# BoostStage.net
KiCad netlist of a schematic drawn in Altium Designer
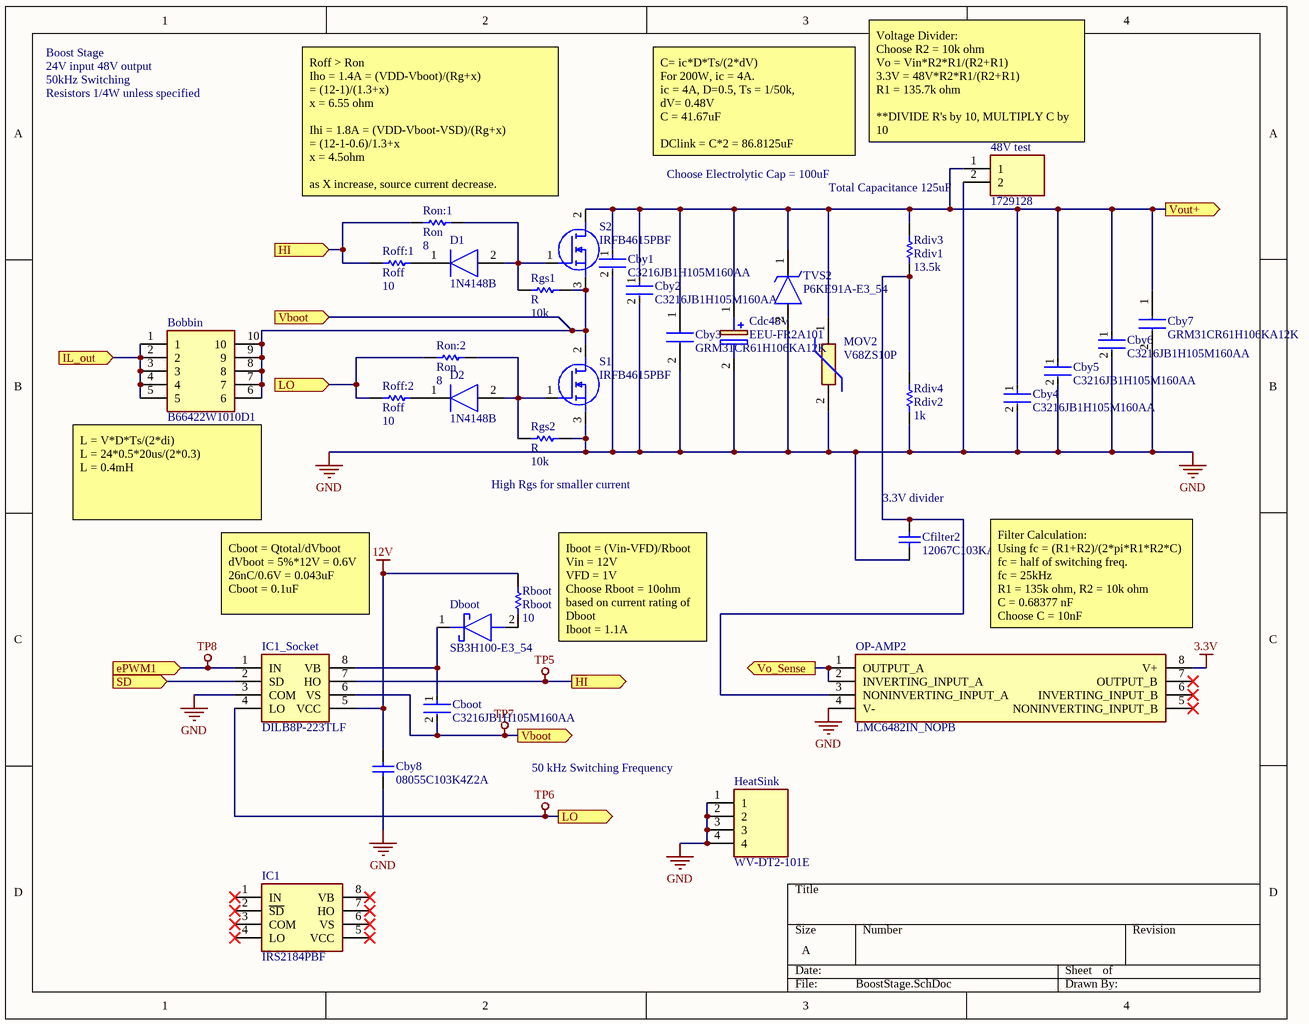
[diagram p0: BoostStage.SchDoc]

(export (version "E")
  (design (tool "Eeschema 10.0.6"))
  (components
    (comp (ref "48V test")
      (value "1729128")
      (footprint "SamacSys:HDRV2W110P0X508_1X2_1016X810X1000P")
      (description "Connector")
      (fields (field (name "MOUSER PART NUMBER") "651-1729128"))
      (libsource (lib "*") (part "1729128"))
    )
    (comp (ref "Bobbin")
      (value "B66422W1010D1")
      (footprint "B66422W1010D1")
      (description "Bobbin")
      (fields (field (name "MOUSER2 PART NUMBER") "871-B66422W1010D1"))
      (libsource (lib "ee_453_yourname") (part "B66422W1010D1"))
    )
    (comp (ref "Cboot")
      (value "C3216JB1H105M160AA")
      (footprint "FP-C3216-160-0_2-IPC_B")
      (description "Multilayer Ceramic Capacitors 1uF ±20% 50V JB SMD 1206")
      (fields (field (name "TOLERANCE") "20%"))
      (libsource (lib "Altium Content Vault") (part "11868f565c42a9108669ba33697ecf6"))
    )
    (comp (ref "Cby1")
      (value "C3216JB1H105M160AA")
      (footprint "FP-C3216-160-0_2-IPC_B")
      (description "Multilayer Ceramic Capacitors 1uF ±20% 50V JB SMD 1206")
      (fields (field (name "TOLERANCE") "20%"))
      (libsource (lib "Altium Content Vault") (part "11868f565c42a9108669ba33697ecf6"))
    )
    (comp (ref "Cby2")
      (value "C3216JB1H105M160AA")
      (footprint "FP-C3216-160-0_2-IPC_B")
      (description "Multilayer Ceramic Capacitors 1uF ±20% 50V JB SMD 1206")
      (fields (field (name "TOLERANCE") "20%"))
      (libsource (lib "Altium Content Vault") (part "11868f565c42a9108669ba33697ecf6"))
    )
    (comp (ref "Cby3")
      (value "GRM31CR61H106KA12K")
      (footprint "SamacSys:CAPC3216X180N")
      (description "Capacitor Ceramic 10uF")
      (fields (field (name "MOUSER PART NUMBER") "81-GRM31CR61H106KA2K"))
      (libsource (lib "*") (part "GRM31CR61H106KA12K"))
    )
    (comp (ref "Cby4")
      (value "C3216JB1H105M160AA")
      (footprint "FP-C3216-160-0_2-IPC_B")
      (description "Multilayer Ceramic Capacitors 1uF ±20% 50V JB SMD 1206")
      (fields (field (name "TOLERANCE") "20%"))
      (libsource (lib "Altium Content Vault") (part "11868f565c42a9108669ba33697ecf6"))
    )
    (comp (ref "Cby5")
      (value "C3216JB1H105M160AA")
      (footprint "FP-C3216-160-0_2-IPC_B")
      (description "Multilayer Ceramic Capacitors 1uF ±20% 50V JB SMD 1206")
      (fields (field (name "TOLERANCE") "20%"))
      (libsource (lib "Altium Content Vault") (part "11868f565c42a9108669ba33697ecf6"))
    )
    (comp (ref "Cby6")
      (value "C3216JB1H105M160AA")
      (footprint "FP-C3216-160-0_2-IPC_B")
      (description "Multilayer Ceramic Capacitors 1uF ±20% 50V JB SMD 1206")
      (fields (field (name "TOLERANCE") "20%"))
      (libsource (lib "Altium Content Vault") (part "11868f565c42a9108669ba33697ecf6"))
    )
    (comp (ref "Cby7")
      (value "GRM31CR61H106KA12K")
      (footprint "SamacSys:CAPC3216X180N")
      (description "Capacitor Ceramic 10uF")
      (fields (field (name "MOUSER PART NUMBER") "81-GRM31CR61H106KA2K"))
      (libsource (lib "*") (part "GRM31CR61H106KA12K"))
    )
    (comp (ref "Cby8")
      (value "08055C103K4Z2A")
      (footprint "CAPC2013X94X50NL20T25")
      (fields (field (name "MANUFACTURER") "AVX Interconnect / Elco"))
      (libsource (lib "Altium Content Vault") (part "CAP"))
    )
    (comp (ref "Cdc48V")
      (value "EEU-FR2A101")
      (footprint "SamacSys:CAPPRD500W65D1000H2200")
      (description "100uF Capacitor Polarised")
      (fields (field (name "MOUSER PART NUMBER") "667-EEU-FR2A101"))
      (libsource (lib "*") (part "EEU-FR2A101"))
    )
    (comp (ref "Cfilter2")
      (value "12067C103KAT2A")
      (footprint "CAPC1206(3216)170_N")
      (description "CAP 10nF 500V ±10% 1206 (3216 Metric) Thickness 1.7mm SMD")
      (fields (field (name "TOLERANCE") "Â±10%"))
      (libsource (lib "Altium Content Vault") (part "CAP"))
    )
    (comp (ref "D1")
      (value "1N4148B")
      (footprint "SamacSys:DIOAD990W55L340D162")
      (description "Diode")
      (libsource (lib "*") (part "1N4148B"))
    )
    (comp (ref "D2")
      (value "1N4148B")
      (footprint "SamacSys:DIOAD990W55L340D162")
      (description "Diode")
      (libsource (lib "*") (part "1N4148B"))
    )
    (comp (ref "Dboot")
      (value "SB3H100-E3_54")
      (footprint "SamacSys:DIOAD2855W132L835D505")
      (description "Schottky Diode")
      (fields
        (field (name "MANUFACTURER_PART_NUMBER") "SB3H100-E3/54")
        (field (name "MOUSER PART NUMBER") "625-SB3H100-E3")
      )
      (libsource (lib "*") (part "SB3H100-E3_54"))
    )
    (comp (ref "HeatSink")
      (value "WV-DT2-101E")
      (footprint "SamacSys:WVDT2101E")
      (description "Hardware")
      (fields (field (name "MOUSER PART NUMBER") "588-WV-DT2-101E"))
      (libsource (lib "*") (part "WV-DT2-101E"))
    )
    (comp (ref "IC1")
      (value "IRS2184PBF")
      (footprint "SamacSys:DIP762W56P254L988H533Q8N")
      (description "Integrated Circuit")
      (fields (field (name "MOUSER PART NUMBER") "942-IRS2184PBF"))
      (libsource (lib "*") (part "IRS2184PBF"))
    )
    (comp (ref "IC1_Socket")
      (value "DILB8P-223TLF")
      (footprint "DIPS762W60P254L1016H525Q8N")
      (description "Connector")
      (fields (field (name "MOUSER2 PART NUMBER") "649-DILB8P223TLF"))
      (libsource (lib "ee_453_yourname") (part "DILB8P-223TLF"))
    )
    (comp (ref "MOV2")
      (value "V68ZS10P")
      (footprint "SamacSys:V68ZS10P")
      (description "Varistor")
      (fields (field (name "MOUSER PART NUMBER") "576-V68ZS10P"))
      (libsource (lib "*") (part "V68ZS10P"))
    )
    (comp (ref "OP-AMP2")
      (value "LMC6482IN_NOPB")
      (footprint "SamacSys:DIP794W53P254L959H508Q8N")
      (description "Integrated Circuit")
      (fields
        (field (name "MANUFACTURER_PART_NUMBER") "LMC6482IN/NOPB")
        (field (name "MOUSER PART NUMBER") "926-LMC6482IN/NOPB")
      )
      (libsource (lib "*") (part "LMC6482IN_NOPB"))
    )
    (comp (ref "Rboot")
      (value "Rboot")
      (footprint "AXIAL-0.3")
      (description "1/2W 10ohm Resistor")
      (fields (field (name "ALTIUM_VALUE") "10") (field (name "PUBLISHER") "Altium Limited"))
      (libsource (lib "Miscellaneous Devices") (part "Res1"))
    )
    (comp (ref "Rdiv3")
      (value "Rdiv1")
      (footprint "AXIAL-0.3")
      (description "1/4W 135.455k ohm Resistor")
      (fields (field (name "ALTIUM_VALUE") "13.5k") (field (name "PUBLISHER") "Altium Limited"))
      (libsource (lib "Miscellaneous Devices") (part "Res1"))
    )
    (comp (ref "Rdiv4")
      (value "Rdiv2")
      (footprint "AXIAL-0.3")
      (description "1/4W 10k ohm Resistor")
      (fields (field (name "ALTIUM_VALUE") "1k") (field (name "PUBLISHER") "Altium Limited"))
      (libsource (lib "Miscellaneous Devices") (part "Res1"))
    )
    (comp (ref "Rgs1")
      (value "R")
      (footprint "AXIAL-0.3")
      (description "1/4W 10k ohm Resistor")
      (fields (field (name "ALTIUM_VALUE") "10k") (field (name "PUBLISHER") "Altium Limited"))
      (libsource (lib "Miscellaneous Devices") (part "Res1"))
    )
    (comp (ref "Rgs2")
      (value "R")
      (footprint "AXIAL-0.3")
      (description "1/4W 10k ohm Resistor")
      (fields (field (name "ALTIUM_VALUE") "10k") (field (name "PUBLISHER") "Altium Limited"))
      (libsource (lib "Miscellaneous Devices") (part "Res1"))
    )
    (comp (ref "Roff:1")
      (value "Roff")
      (footprint "AXIAL-0.3")
      (description "1/4W 10ohm Resistor")
      (fields (field (name "ALTIUM_VALUE") "10") (field (name "PUBLISHER") "Altium Limited"))
      (libsource (lib "Miscellaneous Devices") (part "Res1"))
    )
    (comp (ref "Roff:2")
      (value "Roff")
      (footprint "AXIAL-0.3")
      (description "1/4W 10ohm Resistor")
      (fields (field (name "ALTIUM_VALUE") "10") (field (name "PUBLISHER") "Altium Limited"))
      (libsource (lib "Miscellaneous Devices") (part "Res1"))
    )
    (comp (ref "Ron:1")
      (value "Ron")
      (footprint "AXIAL-0.3")
      (description "1/4W 8ohm Resistor")
      (fields (field (name "ALTIUM_VALUE") "8") (field (name "PUBLISHER") "Altium Limited"))
      (libsource (lib "Miscellaneous Devices") (part "Res1"))
    )
    (comp (ref "Ron:2")
      (value "Ron")
      (footprint "AXIAL-0.3")
      (description "1/4W 8ohm Resistor")
      (fields (field (name "ALTIUM_VALUE") "8") (field (name "PUBLISHER") "Altium Limited"))
      (libsource (lib "Miscellaneous Devices") (part "Res1"))
    )
    (comp (ref "S1")
      (value "IRFB4615PBF")
      (footprint "SamacSys:TO254P483X1016X1994-3P")
      (description "MOSFET (N-Channel)")
      (fields (field (name "MOUSER PART NUMBER") "942-IRFB4615PBF"))
      (libsource (lib "*") (part "IRFB4615PBF"))
    )
    (comp (ref "S2")
      (value "IRFB4615PBF")
      (footprint "SamacSys:TO254P483X1016X1994-3P")
      (description "MOSFET (N-Channel)")
      (fields (field (name "MOUSER PART NUMBER") "942-IRFB4615PBF"))
      (libsource (lib "*") (part "IRFB4615PBF"))
    )
    (comp (ref "TVS2")
      (value "P6KE91A-E3_54")
      (footprint "SamacSys:DIOAD1910W86L670D310")
      (description "TVS Diode (Uni-directional)")
      (fields (field (name "MANUFACTURER_PART_NUMBER") "P6KE91A-E3/54"))
      (libsource (lib "*") (part "P6KE91A-E3_54"))
    )
  )
  (nets
    (net (code "1") (name "/IL_out") (class "Default")
      (node (ref "Bobbin") (pin "1") (pinfunction "1_1") (pintype "passive"))
      (node (ref "Bobbin") (pin "2") (pinfunction "2_2") (pintype "passive"))
      (node (ref "Bobbin") (pin "3") (pinfunction "3_3") (pintype "passive"))
      (node (ref "Bobbin") (pin "4") (pinfunction "4_4") (pintype "passive"))
      (node (ref "Bobbin") (pin "5") (pinfunction "5_5") (pintype "passive"))
    )
    (net (code "2") (name "/SD") (class "Default")
      (node (ref "IC1_Socket") (pin "2") (pinfunction "SD_2") (pintype "passive"))
    )
    (net (code "3") (name "/Vo_Sense") (class "Default")
      (node (ref "OP-AMP2") (pin "1") (pinfunction "OUTPUT_A_1") (pintype "passive"))
      (node (ref "OP-AMP2") (pin "2") (pinfunction "INVERTING_INPUT_A_2") (pintype "passive"))
    )
    (net (code "4") (name "/Vout+") (class "Default")
      (node (ref "48V test") (pin "1") (pinfunction "1_1") (pintype "passive"))
      (node (ref "Cby1") (pin "1") (pinfunction "1_1") (pintype "passive"))
      (node (ref "Cby2") (pin "1") (pinfunction "1_1") (pintype "passive"))
      (node (ref "Cby3") (pin "1") (pinfunction "1_1") (pintype "passive"))
      (node (ref "Cby4") (pin "1") (pinfunction "1_1") (pintype "passive"))
      (node (ref "Cby5") (pin "1") (pinfunction "1_1") (pintype "passive"))
      (node (ref "Cby6") (pin "1") (pinfunction "1_1") (pintype "passive"))
      (node (ref "Cby7") (pin "1") (pinfunction "1_1") (pintype "passive"))
      (node (ref "Cdc48V") (pin "1") (pinfunction "+_1") (pintype "passive"))
      (node (ref "MOV2") (pin "1") (pinfunction "1_1") (pintype "passive"))
      (node (ref "Rdiv3") (pin "2") (pinfunction "2_2") (pintype "passive"))
      (node (ref "S2") (pin "2") (pinfunction "D_2") (pintype "passive"))
      (node (ref "TVS2") (pin "1") (pinfunction "K_1") (pintype "passive"))
    )
    (net (code "5") (name "3.3V") (class "Default")
      (node (ref "OP-AMP2") (pin "8") (pinfunction "V+_8") (pintype "passive"))
    )
    (net (code "6") (name "12V") (class "Default")
      (node (ref "Cby8") (pin "1") (pinfunction "1_1") (pintype "passive"))
      (node (ref "IC1_Socket") (pin "5") (pinfunction "VCC_5") (pintype "passive"))
      (node (ref "Rboot") (pin "2") (pinfunction "2_2") (pintype "passive"))
    )
    (net (code "7") (name "GND") (class "Default")
      (node (ref "48V test") (pin "2") (pinfunction "2_2") (pintype "passive"))
      (node (ref "Cby1") (pin "2") (pinfunction "2_2") (pintype "passive"))
      (node (ref "Cby2") (pin "2") (pinfunction "2_2") (pintype "passive"))
      (node (ref "Cby3") (pin "2") (pinfunction "2_2") (pintype "passive"))
      (node (ref "Cby4") (pin "2") (pinfunction "2_2") (pintype "passive"))
      (node (ref "Cby5") (pin "2") (pinfunction "2_2") (pintype "passive"))
      (node (ref "Cby6") (pin "2") (pinfunction "2_2") (pintype "passive"))
      (node (ref "Cby7") (pin "2") (pinfunction "2_2") (pintype "passive"))
      (node (ref "Cby8") (pin "2") (pinfunction "2_2") (pintype "passive"))
      (node (ref "Cdc48V") (pin "2") (pinfunction "-_2") (pintype "passive"))
      (node (ref "Cfilter2") (pin "1") (pinfunction "1_1") (pintype "passive"))
      (node (ref "HeatSink") (pin "1") (pinfunction "1_1") (pintype "passive"))
      (node (ref "HeatSink") (pin "2") (pinfunction "2_2") (pintype "passive"))
      (node (ref "HeatSink") (pin "3") (pinfunction "3_3") (pintype "passive"))
      (node (ref "HeatSink") (pin "4") (pinfunction "4_4") (pintype "passive"))
      (node (ref "IC1_Socket") (pin "3") (pinfunction "COM_3") (pintype "passive"))
      (node (ref "MOV2") (pin "2") (pinfunction "2_2") (pintype "passive"))
      (node (ref "OP-AMP2") (pin "4") (pinfunction "V-_4") (pintype "passive"))
      (node (ref "Rdiv4") (pin "1") (pinfunction "1_1") (pintype "passive"))
      (node (ref "Rgs2") (pin "2") (pinfunction "2_2") (pintype "passive"))
      (node (ref "S1") (pin "3") (pinfunction "S_3") (pintype "passive"))
      (node (ref "TVS2") (pin "2") (pinfunction "A_2") (pintype "passive"))
    )
    (net (code "8") (name "Net-(D1-A)") (class "Default")
      (node (ref "D1") (pin "2") (pinfunction "A_2") (pintype "passive"))
      (node (ref "Rgs1") (pin "1") (pinfunction "1_1") (pintype "passive"))
      (node (ref "Ron:1") (pin "2") (pinfunction "2_2") (pintype "passive"))
      (node (ref "S2") (pin "1") (pinfunction "G_1") (pintype "passive"))
    )
    (net (code "9") (name "Net-(D1-K)") (class "Default")
      (node (ref "D1") (pin "1") (pinfunction "K_1") (pintype "passive"))
      (node (ref "Roff:1") (pin "2") (pinfunction "2_2") (pintype "passive"))
    )
    (net (code "10") (name "Net-(D2-A)") (class "Default")
      (node (ref "D2") (pin "2") (pinfunction "A_2") (pintype "passive"))
      (node (ref "Rgs2") (pin "1") (pinfunction "1_1") (pintype "passive"))
      (node (ref "Ron:2") (pin "2") (pinfunction "2_2") (pintype "passive"))
      (node (ref "S1") (pin "1") (pinfunction "G_1") (pintype "passive"))
    )
    (net (code "11") (name "Net-(D2-K)") (class "Default")
      (node (ref "D2") (pin "1") (pinfunction "K_1") (pintype "passive"))
      (node (ref "Roff:2") (pin "2") (pinfunction "2_2") (pintype "passive"))
    )
    (net (code "12") (name "Net-(Dboot-A)") (class "Default")
      (node (ref "Dboot") (pin "2") (pinfunction "A_2") (pintype "passive"))
      (node (ref "Rboot") (pin "1") (pinfunction "1_1") (pintype "passive"))
    )
    (net (code "13") (name "Net-(Dboot-K)") (class "Default")
      (node (ref "Cboot") (pin "1") (pinfunction "1_1") (pintype "passive"))
      (node (ref "Dboot") (pin "1") (pinfunction "K_1") (pintype "passive"))
      (node (ref "IC1_Socket") (pin "8") (pinfunction "VB_8") (pintype "passive"))
    )
    (net (code "14") (name "Net-(OP-AMP2-NONINVERTING_INPUT_A)") (class "Default")
      (node (ref "Cfilter2") (pin "2") (pinfunction "2_2") (pintype "passive"))
      (node (ref "OP-AMP2") (pin "3") (pinfunction "NONINVERTING_INPUT_A_3") (pintype "passive"))
      (node (ref "Rdiv3") (pin "1") (pinfunction "1_1") (pintype "passive"))
      (node (ref "Rdiv4") (pin "2") (pinfunction "2_2") (pintype "passive"))
    )
    (net (code "15") (name "TP5") (class "Default")
      (node (ref "IC1_Socket") (pin "7") (pinfunction "HO_7") (pintype "passive"))
      (node (ref "Roff:1") (pin "1") (pinfunction "1_1") (pintype "passive"))
      (node (ref "Ron:1") (pin "1") (pinfunction "1_1") (pintype "passive"))
    )
    (net (code "16") (name "TP6") (class "Default")
      (node (ref "IC1_Socket") (pin "4") (pinfunction "LO_4") (pintype "passive"))
      (node (ref "Roff:2") (pin "1") (pinfunction "1_1") (pintype "passive"))
      (node (ref "Ron:2") (pin "1") (pinfunction "1_1") (pintype "passive"))
    )
    (net (code "17") (name "TP7") (class "Default")
      (node (ref "Bobbin") (pin "10") (pinfunction "10_10") (pintype "passive"))
      (node (ref "Bobbin") (pin "6") (pinfunction "6_6") (pintype "passive"))
      (node (ref "Bobbin") (pin "7") (pinfunction "7_7") (pintype "passive"))
      (node (ref "Bobbin") (pin "8") (pinfunction "8_8") (pintype "passive"))
      (node (ref "Bobbin") (pin "9") (pinfunction "9_9") (pintype "passive"))
      (node (ref "Cboot") (pin "2") (pinfunction "2_2") (pintype "passive"))
      (node (ref "IC1_Socket") (pin "6") (pinfunction "VS_6") (pintype "passive"))
      (node (ref "Rgs1") (pin "2") (pinfunction "2_2") (pintype "passive"))
      (node (ref "S1") (pin "2") (pinfunction "D_2") (pintype "passive"))
      (node (ref "S2") (pin "3") (pinfunction "S_3") (pintype "passive"))
    )
    (net (code "18") (name "TP8") (class "Default")
      (node (ref "IC1_Socket") (pin "1") (pinfunction "IN_1") (pintype "passive"))
    )
    (net (code "19") (name "unconnected-(IC1-COM-Pad3)") (class "Default")
      (node (ref "IC1") (pin "3") (pinfunction "COM_3") (pintype "passive+no_connect"))
    )
    (net (code "20") (name "unconnected-(IC1-HO-Pad7)") (class "Default")
      (node (ref "IC1") (pin "7") (pinfunction "HO_7") (pintype "passive+no_connect"))
    )
    (net (code "21") (name "unconnected-(IC1-IN-Pad1)") (class "Default")
      (node (ref "IC1") (pin "1") (pinfunction "IN_1") (pintype "passive+no_connect"))
    )
    (net (code "22") (name "unconnected-(IC1-LO-Pad4)") (class "Default")
      (node (ref "IC1") (pin "4") (pinfunction "LO_4") (pintype "passive+no_connect"))
    )
    (net (code "23") (name "unconnected-(IC1-VB-Pad8)") (class "Default")
      (node (ref "IC1") (pin "8") (pinfunction "VB_8") (pintype "passive+no_connect"))
    )
    (net (code "24") (name "unconnected-(IC1-VCC-Pad5)") (class "Default")
      (node (ref "IC1") (pin "5") (pinfunction "VCC_5") (pintype "passive+no_connect"))
    )
    (net (code "25") (name "unconnected-(IC1-VS-Pad6)") (class "Default")
      (node (ref "IC1") (pin "6") (pinfunction "VS_6") (pintype "passive+no_connect"))
    )
    (net (code "26") (name "unconnected-(IC1-~{SD}-Pad2)") (class "Default")
      (node (ref "IC1") (pin "2") (pinfunction "~{SD}_2") (pintype "passive+no_connect"))
    )
    (net (code "27") (name "unconnected-(OP-AMP2-INVERTING_INPUT_B-Pad6)") (class "Default")
      (node (ref "OP-AMP2") (pin "6") (pinfunction "INVERTING_INPUT_B_6") (pintype "passive+no_connect"))
    )
    (net (code "28") (name "unconnected-(OP-AMP2-NONINVERTING_INPUT_B-Pad5)") (class "Default")
      (node (ref "OP-AMP2") (pin "5") (pinfunction "NONINVERTING_INPUT_B_5") (pintype "passive+no_connect"))
    )
    (net (code "29") (name "unconnected-(OP-AMP2-OUTPUT_B-Pad7)") (class "Default")
      (node (ref "OP-AMP2") (pin "7") (pinfunction "OUTPUT_B_7") (pintype "passive+no_connect"))
    )
  )
)
